# vcu.net
KiCad netlist of a schematic drawn in EAGLE
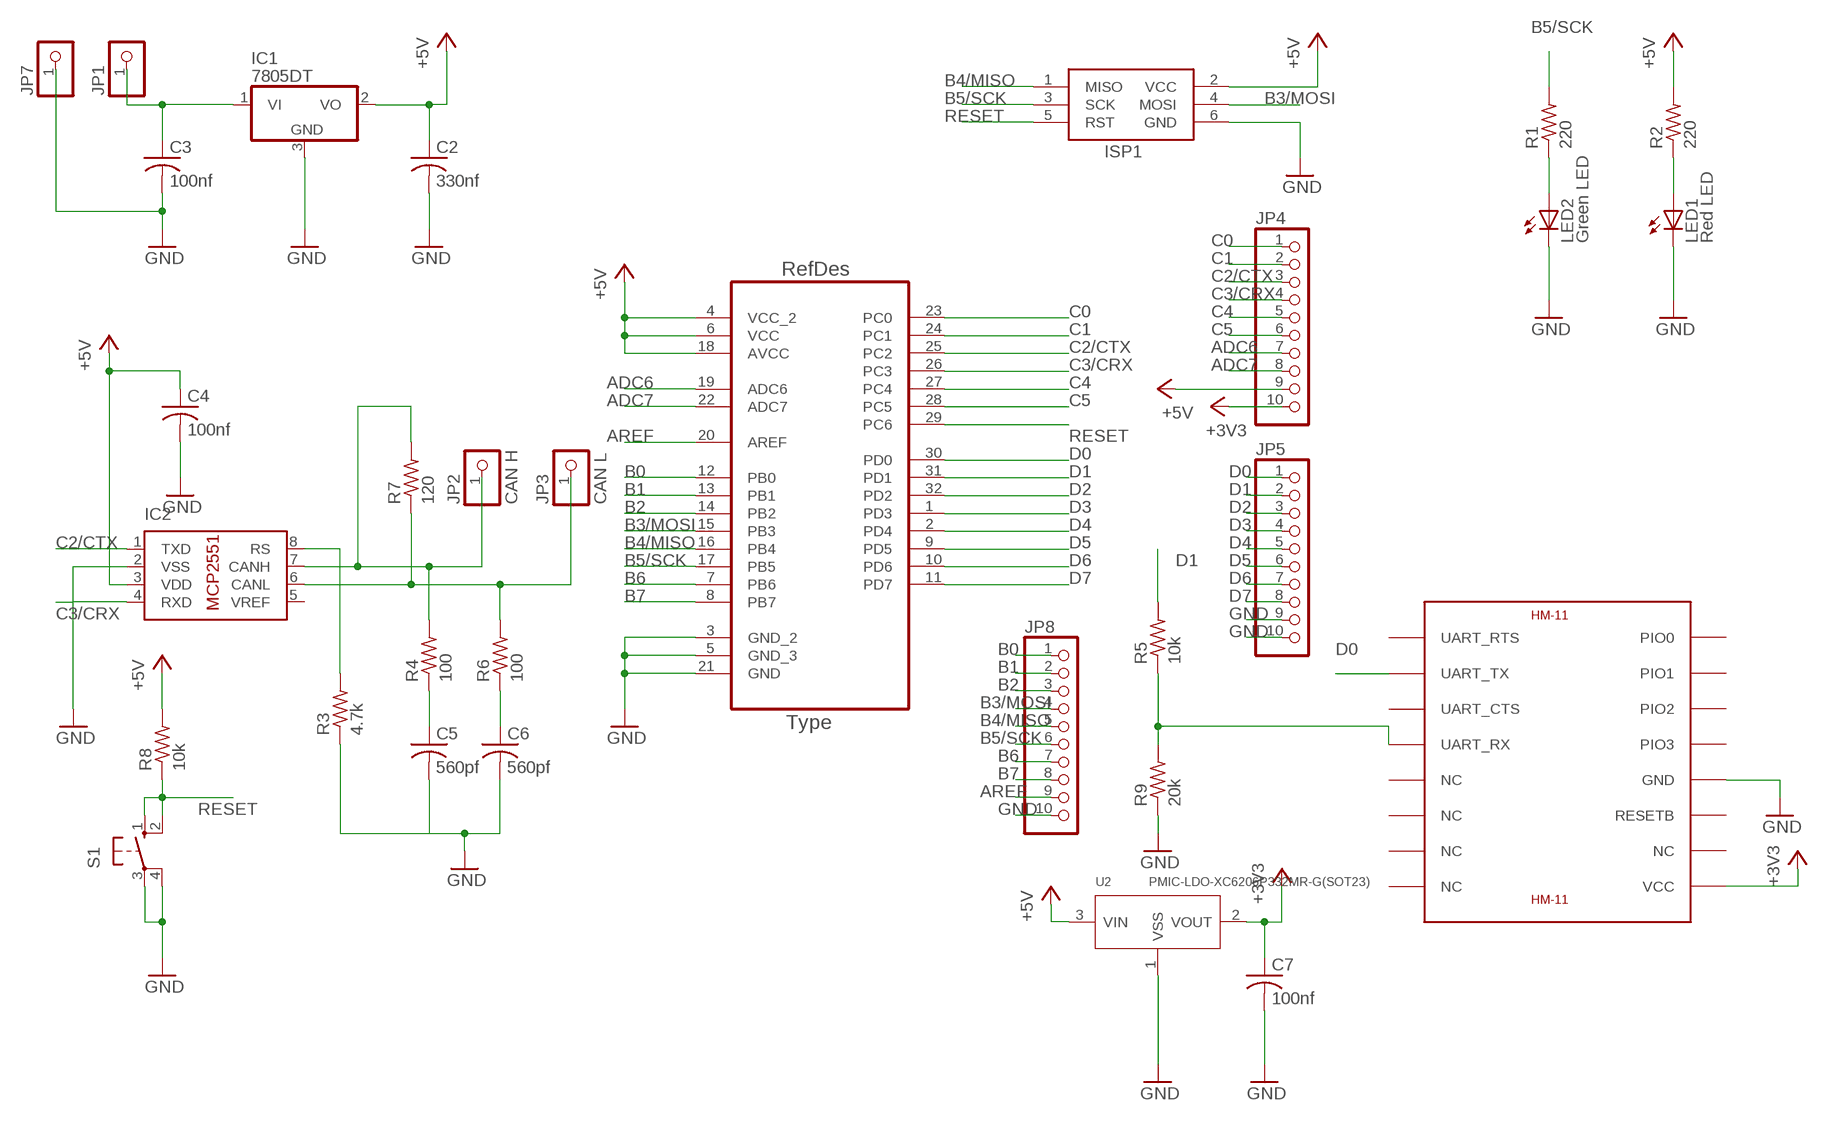
[diagram p0: schematic, sheet 1]

(export (version "E")
  (design (tool "Eeschema 10.0.6"))
  (components
    (comp (ref "C2")
      (value "330nf")
      (footprint "eagle-import:C0402")
      (libsource (lib "eagle-import") (part "C-USC0402"))
    )
    (comp (ref "C3")
      (value "100nf")
      (footprint "eagle-import:C0402")
      (libsource (lib "eagle-import") (part "C-USC0402"))
    )
    (comp (ref "C4")
      (value "100nf")
      (footprint "eagle-import:C0402")
      (libsource (lib "eagle-import") (part "C-USC0402"))
    )
    (comp (ref "C5")
      (value "560pf")
      (footprint "eagle-import:C0402")
      (libsource (lib "eagle-import") (part "C-USC0402"))
    )
    (comp (ref "C6")
      (value "560pf")
      (footprint "eagle-import:C0402")
      (libsource (lib "eagle-import") (part "C-USC0402"))
    )
    (comp (ref "C7")
      (value "100nf")
      (footprint "eagle-import:C0402")
      (libsource (lib "eagle-import") (part "C-USC0402"))
    )
    (comp (ref "IC1")
      (value "7805DT")
      (footprint "eagle-import:TO252")
      (libsource (lib "eagle-import") (part "78DT05"))
    )
    (comp (ref "IC2")
      (value "MCP2551/SN")
      (footprint "eagle-import:SO08")
      (libsource (lib "eagle-import") (part "MCP2551/SN"))
    )
    (comp (ref "ISP1")
      (value "AVRISP-6")
      (footprint "eagle-import:AVRISP")
      (libsource (lib "eagle-import") (part "AVRISP-6"))
    )
    (comp (ref "JP1")
      (value "PINHD-1X1CB")
      (footprint "eagle-import:1X01-CLEANBIG")
      (libsource (lib "eagle-import") (part "PINHD-1X1CB"))
    )
    (comp (ref "JP2")
      (value "CAN H")
      (footprint "eagle-import:1X01-CLEANBIG")
      (libsource (lib "eagle-import") (part "PINHD-1X1CB"))
    )
    (comp (ref "JP3")
      (value "CAN L")
      (footprint "eagle-import:1X01-CLEANBIG")
      (libsource (lib "eagle-import") (part "PINHD-1X1CB"))
    )
    (comp (ref "JP4")
      (value "PINHD-1X10")
      (footprint "eagle-import:1X10")
      (libsource (lib "eagle-import") (part "PINHD-1X10"))
    )
    (comp (ref "JP5")
      (value "PINHD-1X10")
      (footprint "eagle-import:1X10")
      (libsource (lib "eagle-import") (part "PINHD-1X10"))
    )
    (comp (ref "JP7")
      (value "PINHD-1X1CB")
      (footprint "eagle-import:1X01-CLEANBIG")
      (libsource (lib "eagle-import") (part "PINHD-1X1CB"))
    )
    (comp (ref "JP8")
      (value "PINHD-1X10")
      (footprint "eagle-import:1X10")
      (libsource (lib "eagle-import") (part "PINHD-1X10"))
    )
    (comp (ref "LED1")
      (value "Red LED")
      (footprint "eagle-import:LED-0603")
      (libsource (lib "eagle-import") (part "LED0603"))
    )
    (comp (ref "LED2")
      (value "Green LED")
      (footprint "eagle-import:LED-0603")
      (libsource (lib "eagle-import") (part "LED0603"))
    )
    (comp (ref "R1")
      (value "220")
      (footprint "eagle-import:M0805")
      (libsource (lib "eagle-import") (part "R-US_M0805"))
    )
    (comp (ref "R2")
      (value "220")
      (footprint "eagle-import:M0805")
      (libsource (lib "eagle-import") (part "R-US_M0805"))
    )
    (comp (ref "R3")
      (value "4.7k")
      (footprint "eagle-import:M0805")
      (libsource (lib "eagle-import") (part "R-US_M0805"))
    )
    (comp (ref "R4")
      (value "100")
      (footprint "eagle-import:M0805")
      (libsource (lib "eagle-import") (part "R-US_M0805"))
    )
    (comp (ref "R5")
      (value "10k")
      (footprint "eagle-import:M0805")
      (libsource (lib "eagle-import") (part "R-US_M0805"))
    )
    (comp (ref "R6")
      (value "100")
      (footprint "eagle-import:M0805")
      (libsource (lib "eagle-import") (part "R-US_M0805"))
    )
    (comp (ref "R7")
      (value "120")
      (footprint "eagle-import:M0805")
      (libsource (lib "eagle-import") (part "R-US_M0805"))
    )
    (comp (ref "R8")
      (value "10k")
      (footprint "eagle-import:M0805")
      (libsource (lib "eagle-import") (part "R-US_M0805"))
    )
    (comp (ref "R9")
      (value "20k")
      (footprint "eagle-import:M0805")
      (libsource (lib "eagle-import") (part "R-US_M0805"))
    )
    (comp (ref "S1")
      (value "10-XX")
      (footprint "eagle-import:B3F-10XX")
      (fields (field (name "MPN") "B3F-1000"))
      (libsource (lib "eagle-import") (part "10-XX"))
    )
    (comp (ref "U$1")
      (value "HM-11")
      (footprint "eagle-import:HM-11")
      (libsource (lib "eagle-import") (part "HM-11"))
    )
    (comp (ref "U1")
      (value "ATMEGA328P-AU")
      (footprint "eagle-import:QFP80P900X900X120-32N")
      (libsource (lib "eagle-import") (part "ATMEGA328P-AU"))
    )
    (comp (ref "U2")
      (value "PMIC-LDO-XC6206P332MR-G(SOT23)")
      (footprint "eagle-import:SOT-23")
      (fields (field (name "MF") "Torex") (field (name "MP") "XC6206P332MR-G"))
      (libsource (lib "eagle-import") (part "PMIC-LDO-XC6206P332MR-G(SOT23)"))
    )
  )
  (nets
    (net (code "1") (name "+3V3") (class "Default")
      (node (ref "C7") (pin "1") (pinfunction "1_1") (pintype "passive"))
      (node (ref "JP4") (pin "10") (pinfunction "10_10") (pintype "passive"))
      (node (ref "U$1") (pin "VCC") (pinfunction "VCC_VCC") (pintype "bidirectional"))
      (node (ref "U2") (pin "2") (pinfunction "VOUT_2") (pintype "output"))
    )
    (net (code "2") (name "+5V") (class "Default")
      (node (ref "C2") (pin "1") (pinfunction "1_1") (pintype "passive"))
      (node (ref "C4") (pin "1") (pinfunction "1_1") (pintype "passive"))
      (node (ref "IC1") (pin "2") (pinfunction "VO_2") (pintype "passive"))
      (node (ref "IC2") (pin "3") (pinfunction "VDD_3") (pintype "power_in"))
      (node (ref "ISP1") (pin "2") (pinfunction "VCC_2") (pintype "power_in"))
      (node (ref "JP4") (pin "9") (pinfunction "9_9") (pintype "passive"))
      (node (ref "R2") (pin "2") (pinfunction "2_2") (pintype "passive"))
      (node (ref "R8") (pin "2") (pinfunction "2_2") (pintype "passive"))
      (node (ref "U1") (pin "18") (pinfunction "AVCC_18") (pintype "power_in"))
      (node (ref "U1") (pin "4") (pinfunction "VCC_2_4") (pintype "power_in"))
      (node (ref "U1") (pin "6") (pinfunction "VCC_6") (pintype "power_in"))
      (node (ref "U2") (pin "3") (pinfunction "VIN_3") (pintype "input"))
    )
    (net (code "3") (name "/ADC6") (class "Default")
      (node (ref "JP4") (pin "7") (pinfunction "7_7") (pintype "passive"))
      (node (ref "U1") (pin "19") (pinfunction "ADC6_19") (pintype "input"))
    )
    (net (code "4") (name "/ADC7") (class "Default")
      (node (ref "JP4") (pin "8") (pinfunction "8_8") (pintype "passive"))
      (node (ref "U1") (pin "22") (pinfunction "ADC7_22") (pintype "input"))
    )
    (net (code "5") (name "/AREF") (class "Default")
      (node (ref "JP8") (pin "9") (pinfunction "9_9") (pintype "passive"))
      (node (ref "U1") (pin "20") (pinfunction "AREF_20") (pintype "input"))
    )
    (net (code "6") (name "/B0") (class "Default")
      (node (ref "JP8") (pin "1") (pinfunction "1_1") (pintype "passive"))
      (node (ref "U1") (pin "12") (pinfunction "PB0_12") (pintype "bidirectional"))
    )
    (net (code "7") (name "/B1") (class "Default")
      (node (ref "JP8") (pin "2") (pinfunction "2_2") (pintype "passive"))
      (node (ref "U1") (pin "13") (pinfunction "PB1_13") (pintype "bidirectional"))
    )
    (net (code "8") (name "/B2") (class "Default")
      (node (ref "JP8") (pin "3") (pinfunction "3_3") (pintype "passive"))
      (node (ref "U1") (pin "14") (pinfunction "PB2_14") (pintype "bidirectional"))
    )
    (net (code "9") (name "/B3{slash}MOSI") (class "Default")
      (node (ref "ISP1") (pin "4") (pinfunction "MOSI_4") (pintype "output"))
      (node (ref "JP8") (pin "4") (pinfunction "4_4") (pintype "passive"))
      (node (ref "U1") (pin "15") (pinfunction "PB3_15") (pintype "bidirectional"))
    )
    (net (code "10") (name "/B4{slash}MISO") (class "Default")
      (node (ref "ISP1") (pin "1") (pinfunction "MISO_1") (pintype "input"))
      (node (ref "JP8") (pin "5") (pinfunction "5_5") (pintype "passive"))
      (node (ref "U1") (pin "16") (pinfunction "PB4_16") (pintype "bidirectional"))
    )
    (net (code "11") (name "/B5{slash}SCK") (class "Default")
      (node (ref "ISP1") (pin "3") (pinfunction "SCK_3") (pintype "output"))
      (node (ref "JP8") (pin "6") (pinfunction "6_6") (pintype "passive"))
      (node (ref "R1") (pin "2") (pinfunction "2_2") (pintype "passive"))
      (node (ref "U1") (pin "17") (pinfunction "PB5_17") (pintype "bidirectional"))
    )
    (net (code "12") (name "/B6") (class "Default")
      (node (ref "JP8") (pin "7") (pinfunction "7_7") (pintype "passive"))
      (node (ref "U1") (pin "7") (pinfunction "PB6_7") (pintype "bidirectional"))
    )
    (net (code "13") (name "/B7") (class "Default")
      (node (ref "JP8") (pin "8") (pinfunction "8_8") (pintype "passive"))
      (node (ref "U1") (pin "8") (pinfunction "PB7_8") (pintype "bidirectional"))
    )
    (net (code "14") (name "/C0") (class "Default")
      (node (ref "JP4") (pin "1") (pinfunction "1_1") (pintype "passive"))
      (node (ref "U1") (pin "23") (pinfunction "PC0_23") (pintype "bidirectional"))
    )
    (net (code "15") (name "/C1") (class "Default")
      (node (ref "JP4") (pin "2") (pinfunction "2_2") (pintype "passive"))
      (node (ref "U1") (pin "24") (pinfunction "PC1_24") (pintype "bidirectional"))
    )
    (net (code "16") (name "/C2{slash}CTX") (class "Default")
      (node (ref "IC2") (pin "1") (pinfunction "TXD_1") (pintype "input"))
      (node (ref "JP4") (pin "3") (pinfunction "3_3") (pintype "passive"))
      (node (ref "U1") (pin "25") (pinfunction "PC2_25") (pintype "bidirectional"))
    )
    (net (code "17") (name "/C3{slash}CRX") (class "Default")
      (node (ref "IC2") (pin "4") (pinfunction "RXD_4") (pintype "output"))
      (node (ref "JP4") (pin "4") (pinfunction "4_4") (pintype "passive"))
      (node (ref "U1") (pin "26") (pinfunction "PC3_26") (pintype "bidirectional"))
    )
    (net (code "18") (name "/C4") (class "Default")
      (node (ref "JP4") (pin "5") (pinfunction "5_5") (pintype "passive"))
      (node (ref "U1") (pin "27") (pinfunction "PC4_27") (pintype "bidirectional"))
    )
    (net (code "19") (name "/C5") (class "Default")
      (node (ref "JP4") (pin "6") (pinfunction "6_6") (pintype "passive"))
      (node (ref "U1") (pin "28") (pinfunction "PC5_28") (pintype "bidirectional"))
    )
    (net (code "20") (name "/D0") (class "Default")
      (node (ref "JP5") (pin "1") (pinfunction "1_1") (pintype "passive"))
      (node (ref "U$1") (pin "UART_TX") (pinfunction "UART_TX_UART_TX") (pintype "bidirectional"))
      (node (ref "U1") (pin "30") (pinfunction "PD0_30") (pintype "bidirectional"))
    )
    (net (code "21") (name "/D1") (class "Default")
      (node (ref "JP5") (pin "2") (pinfunction "2_2") (pintype "passive"))
      (node (ref "R5") (pin "2") (pinfunction "2_2") (pintype "passive"))
      (node (ref "U1") (pin "31") (pinfunction "PD1_31") (pintype "bidirectional"))
    )
    (net (code "22") (name "/D2") (class "Default")
      (node (ref "JP5") (pin "3") (pinfunction "3_3") (pintype "passive"))
      (node (ref "U1") (pin "32") (pinfunction "PD2_32") (pintype "bidirectional"))
    )
    (net (code "23") (name "/D3") (class "Default")
      (node (ref "JP5") (pin "4") (pinfunction "4_4") (pintype "passive"))
      (node (ref "U1") (pin "1") (pinfunction "PD3_1") (pintype "bidirectional"))
    )
    (net (code "24") (name "/D4") (class "Default")
      (node (ref "JP5") (pin "5") (pinfunction "5_5") (pintype "passive"))
      (node (ref "U1") (pin "2") (pinfunction "PD4_2") (pintype "bidirectional"))
    )
    (net (code "25") (name "/D5") (class "Default")
      (node (ref "JP5") (pin "6") (pinfunction "6_6") (pintype "passive"))
      (node (ref "U1") (pin "9") (pinfunction "PD5_9") (pintype "bidirectional"))
    )
    (net (code "26") (name "/D6") (class "Default")
      (node (ref "JP5") (pin "7") (pinfunction "7_7") (pintype "passive"))
      (node (ref "U1") (pin "10") (pinfunction "PD6_10") (pintype "bidirectional"))
    )
    (net (code "27") (name "/D7") (class "Default")
      (node (ref "JP5") (pin "8") (pinfunction "8_8") (pintype "passive"))
      (node (ref "U1") (pin "11") (pinfunction "PD7_11") (pintype "bidirectional"))
    )
    (net (code "28") (name "/RESET") (class "Default")
      (node (ref "ISP1") (pin "5") (pinfunction "RST_5") (pintype "output"))
      (node (ref "R8") (pin "1") (pinfunction "1_1") (pintype "passive"))
      (node (ref "S1") (pin "1") (pinfunction "S_1") (pintype "passive"))
      (node (ref "S1") (pin "2") (pinfunction "S1_2") (pintype "passive"))
      (node (ref "U1") (pin "29") (pinfunction "PC6_29") (pintype "bidirectional"))
    )
    (net (code "29") (name "GND") (class "Default")
      (node (ref "C2") (pin "2") (pinfunction "2_2") (pintype "passive"))
      (node (ref "C3") (pin "2") (pinfunction "2_2") (pintype "passive"))
      (node (ref "C4") (pin "2") (pinfunction "2_2") (pintype "passive"))
      (node (ref "C5") (pin "2") (pinfunction "2_2") (pintype "passive"))
      (node (ref "C6") (pin "2") (pinfunction "2_2") (pintype "passive"))
      (node (ref "C7") (pin "2") (pinfunction "2_2") (pintype "passive"))
      (node (ref "IC1") (pin "3") (pinfunction "GND_3") (pintype "passive"))
      (node (ref "IC2") (pin "2") (pinfunction "VSS_2") (pintype "power_in"))
      (node (ref "ISP1") (pin "6") (pinfunction "GND_6") (pintype "power_in"))
      (node (ref "JP5") (pin "10") (pinfunction "10_10") (pintype "passive"))
      (node (ref "JP5") (pin "9") (pinfunction "9_9") (pintype "passive"))
      (node (ref "JP7") (pin "1") (pinfunction "1_1") (pintype "passive"))
      (node (ref "JP8") (pin "10") (pinfunction "10_10") (pintype "passive"))
      (node (ref "LED1") (pin "C") (pinfunction "C_C") (pintype "passive"))
      (node (ref "LED2") (pin "C") (pinfunction "C_C") (pintype "passive"))
      (node (ref "R3") (pin "1") (pinfunction "1_1") (pintype "passive"))
      (node (ref "R9") (pin "1") (pinfunction "1_1") (pintype "passive"))
      (node (ref "S1") (pin "3") (pinfunction "P_3") (pintype "passive"))
      (node (ref "S1") (pin "4") (pinfunction "P1_4") (pintype "passive"))
      (node (ref "U$1") (pin "GND") (pinfunction "GND_GND") (pintype "bidirectional"))
      (node (ref "U1") (pin "21") (pinfunction "GND_21") (pintype "passive"))
      (node (ref "U1") (pin "3") (pinfunction "GND_2_3") (pintype "passive"))
      (node (ref "U1") (pin "5") (pinfunction "GND_3_5") (pintype "passive"))
      (node (ref "U2") (pin "1") (pinfunction "VSS_1") (pintype "power_in"))
    )
    (net (code "30") (name "Net-(C5-Pad1)") (class "Default")
      (node (ref "C5") (pin "1") (pinfunction "1_1") (pintype "passive"))
      (node (ref "R4") (pin "1") (pinfunction "1_1") (pintype "passive"))
    )
    (net (code "31") (name "Net-(C6-Pad1)") (class "Default")
      (node (ref "C6") (pin "1") (pinfunction "1_1") (pintype "passive"))
      (node (ref "R6") (pin "1") (pinfunction "1_1") (pintype "passive"))
    )
    (net (code "32") (name "Net-(IC1-VI)") (class "Default")
      (node (ref "C3") (pin "1") (pinfunction "1_1") (pintype "passive"))
      (node (ref "IC1") (pin "1") (pinfunction "VI_1") (pintype "input"))
      (node (ref "JP1") (pin "1") (pinfunction "1_1") (pintype "passive"))
    )
    (net (code "33") (name "Net-(IC2-CANH)") (class "Default")
      (node (ref "IC2") (pin "7") (pinfunction "CANH_7") (pintype "bidirectional"))
      (node (ref "JP2") (pin "1") (pinfunction "1_1") (pintype "passive"))
      (node (ref "R4") (pin "2") (pinfunction "2_2") (pintype "passive"))
      (node (ref "R7") (pin "2") (pinfunction "2_2") (pintype "passive"))
    )
    (net (code "34") (name "Net-(IC2-CANL)") (class "Default")
      (node (ref "IC2") (pin "6") (pinfunction "CANL_6") (pintype "bidirectional"))
      (node (ref "JP3") (pin "1") (pinfunction "1_1") (pintype "passive"))
      (node (ref "R6") (pin "2") (pinfunction "2_2") (pintype "passive"))
      (node (ref "R7") (pin "1") (pinfunction "1_1") (pintype "passive"))
    )
    (net (code "35") (name "Net-(IC2-RS)") (class "Default")
      (node (ref "IC2") (pin "8") (pinfunction "RS_8") (pintype "input"))
      (node (ref "R3") (pin "2") (pinfunction "2_2") (pintype "passive"))
    )
    (net (code "36") (name "Net-(LED1-PadA)") (class "Default")
      (node (ref "LED1") (pin "A") (pinfunction "A_A") (pintype "passive"))
      (node (ref "R2") (pin "1") (pinfunction "1_1") (pintype "passive"))
    )
    (net (code "37") (name "Net-(LED2-PadA)") (class "Default")
      (node (ref "LED2") (pin "A") (pinfunction "A_A") (pintype "passive"))
      (node (ref "R1") (pin "1") (pinfunction "1_1") (pintype "passive"))
    )
    (net (code "38") (name "Net-(R5-Pad1)") (class "Default")
      (node (ref "R5") (pin "1") (pinfunction "1_1") (pintype "passive"))
      (node (ref "R9") (pin "2") (pinfunction "2_2") (pintype "passive"))
      (node (ref "U$1") (pin "UART_RX") (pinfunction "UART_RX_UART_RX") (pintype "bidirectional"))
    )
    (net (code "39") (name "unconnected-(IC2-VREF-Pad5)") (class "Default")
      (node (ref "IC2") (pin "5") (pinfunction "VREF_5") (pintype "output"))
    )
    (net (code "40") (name "unconnected-(U$1-NC-PadNC@5)") (class "Default")
      (node (ref "U$1") (pin "NC@5") (pinfunction "NC_NC@5") (pintype "bidirectional"))
    )
    (net (code "41") (name "unconnected-(U$1-NC-PadNC@6)") (class "Default")
      (node (ref "U$1") (pin "NC@6") (pinfunction "NC_NC@6") (pintype "bidirectional"))
    )
    (net (code "42") (name "unconnected-(U$1-NC-PadNC@7)") (class "Default")
      (node (ref "U$1") (pin "NC@7") (pinfunction "NC_NC@7") (pintype "bidirectional"))
    )
    (net (code "43") (name "unconnected-(U$1-NC-PadNC@8)") (class "Default")
      (node (ref "U$1") (pin "NC@8") (pinfunction "NC_NC@8") (pintype "bidirectional"))
    )
    (net (code "44") (name "unconnected-(U$1-NC-PadNC@10)") (class "Default")
      (node (ref "U$1") (pin "NC@10") (pinfunction "NC_NC@10") (pintype "bidirectional"))
    )
    (net (code "45") (name "unconnected-(U$1-PadPIO0)") (class "Default")
      (node (ref "U$1") (pin "PIO0") (pinfunction "PIO0_PIO0") (pintype "bidirectional"))
    )
    (net (code "46") (name "unconnected-(U$1-PadPIO1)") (class "Default")
      (node (ref "U$1") (pin "PIO1") (pinfunction "PIO1_PIO1") (pintype "bidirectional"))
    )
    (net (code "47") (name "unconnected-(U$1-PadPIO2)") (class "Default")
      (node (ref "U$1") (pin "PIO2") (pinfunction "PIO2_PIO2") (pintype "bidirectional"))
    )
    (net (code "48") (name "unconnected-(U$1-PadPIO3)") (class "Default")
      (node (ref "U$1") (pin "PIO3") (pinfunction "PIO3_PIO3") (pintype "bidirectional"))
    )
    (net (code "49") (name "unconnected-(U$1-PadRESETB)") (class "Default")
      (node (ref "U$1") (pin "RESETB") (pinfunction "RESETB_RESETB") (pintype "bidirectional"))
    )
    (net (code "50") (name "unconnected-(U$1-PadUART_CTS)") (class "Default")
      (node (ref "U$1") (pin "UART_CTS") (pinfunction "UART_CTS_UART_CTS") (pintype "bidirectional"))
    )
    (net (code "51") (name "unconnected-(U$1-PadUART_RTS)") (class "Default")
      (node (ref "U$1") (pin "UART_RTS") (pinfunction "UART_RTS_UART_RTS") (pintype "bidirectional"))
    )
  )
)
